# CON_CAN_RJ45.net
KiCad netlist of a schematic drawn in Altium Designer
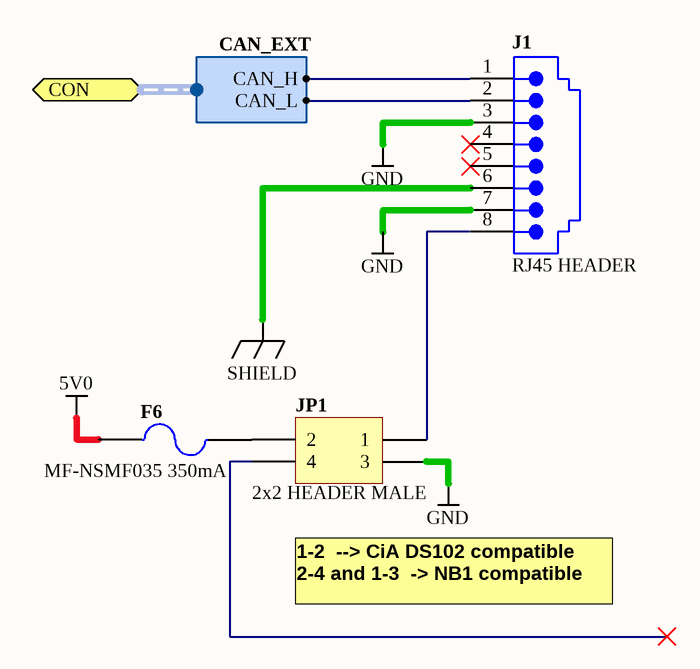
[diagram p0: CON_CAN_RJ45.SchDoc]

(export (version "E")
  (design (tool "Eeschema 10.0.6"))
  (components
    (comp (ref "F6")
      (value "MF-NSMF035 350mA")
      (footprint "RESC3216")
      (description "Multifuse, SMD 1206, 350mA")
      (libsource (lib "AltiumDesignLibrary") (part "MULTIFUSE"))
    )
    (comp (ref "J1")
      (value "RJ45 HEADER")
      (footprint "15-43-6233")
      (description "Connector, RJ45 Socket, Right-Angle, 8 Way (Ethernet), PCM8P8C")
      (libsource (lib "AltiumDesignLibrary") (part "CON-RJ45-8-RA"))
    )
    (comp (ref "JP1")
      (value "2x2 HEADER MALE")
      (footprint "HDR2X2")
      (description "Header IDC, 2 x 2 Pin Vertical 2.54mm Pitch (Non-Boxed, Male)")
      (libsource (lib "AltiumDesignLibrary") (part "CON-HDR-2x2-STR"))
    )
  )
  (nets
    (net (code "2") (name "/CAN_H") (class "Default")
      (node (ref "J1") (pin "1") (pinfunction "1_1") (pintype "passive"))
    )
    (net (code "3") (name "/CAN_L") (class "Default")
      (node (ref "J1") (pin "2") (pinfunction "2_2") (pintype "passive"))
    )
    (net (code "5") (name "5V0") (class "Default")
      (node (ref "F6") (pin "1") (pinfunction "1_1") (pintype "passive"))
    )
    (net (code "6") (name "GND") (class "Default")
      (node (ref "J1") (pin "3") (pinfunction "3_3") (pintype "passive"))
      (node (ref "J1") (pin "7") (pinfunction "7_7") (pintype "passive"))
      (node (ref "JP1") (pin "3") (pinfunction "3_3") (pintype "passive"))
    )
    (net (code "7") (name "Net-(F6-Pad2)") (class "Default")
      (node (ref "F6") (pin "2") (pinfunction "2_2") (pintype "passive"))
      (node (ref "JP1") (pin "2") (pinfunction "2_2") (pintype "passive"))
    )
    (net (code "8") (name "Net-(J1-Pad8)") (class "Default")
      (node (ref "J1") (pin "8") (pinfunction "8_8") (pintype "passive"))
      (node (ref "JP1") (pin "1") (pinfunction "1_1") (pintype "passive"))
    )
    (net (code "9") (name "SHIELD") (class "Default")
      (node (ref "J1") (pin "6") (pinfunction "6_6") (pintype "passive"))
    )
    (net (code "10") (name "unconnected-(J1-Pad4)") (class "Default")
      (node (ref "J1") (pin "4") (pinfunction "4_4") (pintype "passive+no_connect"))
    )
    (net (code "11") (name "unconnected-(J1-Pad5)") (class "Default")
      (node (ref "J1") (pin "5") (pinfunction "5_5") (pintype "passive+no_connect"))
    )
    (net (code "12") (name "unconnected-(JP1-Pad4)") (class "Default")
      (node (ref "JP1") (pin "4") (pinfunction "4_4") (pintype "passive+no_connect"))
    )
  )
)
